# WirelessTempSensor.net
KiCad netlist of a schematic drawn in EAGLE
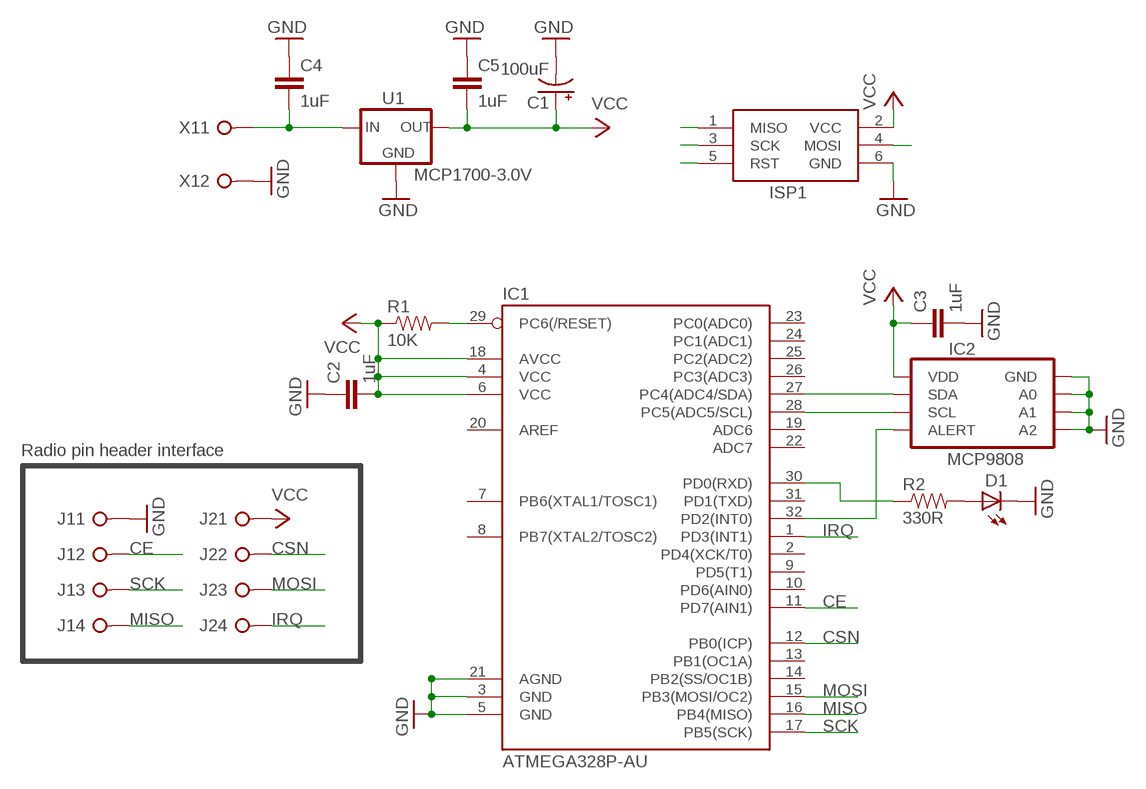
[diagram p0: schematic, sheet 1]

(export (version "E")
  (design (tool "Eeschema 10.0.6"))
  (components
    (comp (ref "C1")
      (value "100uF")
      (footprint "eagle-import:CAP-POL-2.5-6")
      (libsource (lib "eagle-import") (part "CAP-POL-2.5-6"))
    )
    (comp (ref "C2")
      (value "1uF")
      (footprint "eagle-import:CAPACITOR-0805")
      (libsource (lib "eagle-import") (part "CAPACITOR-0805"))
    )
    (comp (ref "C3")
      (value "1uF")
      (footprint "eagle-import:CAPACITOR-0805")
      (libsource (lib "eagle-import") (part "CAPACITOR-0805"))
    )
    (comp (ref "C4")
      (value "1uF")
      (footprint "eagle-import:CAPACITOR-0805")
      (libsource (lib "eagle-import") (part "CAPACITOR-0805"))
    )
    (comp (ref "C5")
      (value "1uF")
      (footprint "eagle-import:CAPACITOR-0805")
      (libsource (lib "eagle-import") (part "CAPACITOR-0805"))
    )
    (comp (ref "D1")
      (value "LED-0805")
      (footprint "eagle-import:LED-0805")
      (libsource (lib "eagle-import") (part "LED-0805"))
    )
    (comp (ref "IC1")
      (value "ATMEGA328P-AU")
      (footprint "eagle-import:QFP32-08")
      (libsource (lib "eagle-import") (part "ATMEGA328P-AU"))
    )
    (comp (ref "IC2")
      (value "MCP9808")
      (footprint "eagle-import:MSOP8-0.65-3X3MM")
      (libsource (lib "eagle-import") (part "MCP9808"))
    )
    (comp (ref "ISP1")
      (value "ICSP-HEADER-6")
      (footprint "eagle-import:ICSP-HEADER")
      (libsource (lib "eagle-import") (part "ICSP-HEADER-6"))
    )
    (comp (ref "J1")
      (value "PINHD-1X4")
      (footprint "eagle-import:1X04")
      (libsource (lib "eagle-import") (part "PINHD-1X4"))
    )
    (comp (ref "J2")
      (value "PINHD-1X4")
      (footprint "eagle-import:1X04")
      (libsource (lib "eagle-import") (part "PINHD-1X4"))
    )
    (comp (ref "R1")
      (value "10K")
      (footprint "eagle-import:RESISTOR-0805")
      (libsource (lib "eagle-import") (part "RESISTOR-0805"))
    )
    (comp (ref "R2")
      (value "330R")
      (footprint "eagle-import:RESISTOR-0805")
      (libsource (lib "eagle-import") (part "RESISTOR-0805"))
    )
    (comp (ref "U1")
      (value "MCP1700-3.0V")
      (footprint "eagle-import:SOT-23-3")
      (libsource (lib "eagle-import") (part "MCP1700-SOT23"))
    )
    (comp (ref "X1")
      (value "SCREW-TERM-2")
      (footprint "eagle-import:SCREW-TERM-2")
      (libsource (lib "eagle-import") (part "SCREW-TERM-2"))
    )
  )
  (nets
    (net (code "1") (name "/CE") (class "Default")
      (node (ref "IC1") (pin "11") (pinfunction "PD7(AIN1)_11") (pintype "bidirectional"))
      (node (ref "J1") (pin "2") (pinfunction "KL_2") (pintype "passive"))
    )
    (net (code "2") (name "/CSN") (class "Default")
      (node (ref "IC1") (pin "12") (pinfunction "PB0(ICP)_12") (pintype "bidirectional"))
      (node (ref "J2") (pin "2") (pinfunction "KL_2") (pintype "passive"))
    )
    (net (code "3") (name "/IRQ") (class "Default")
      (node (ref "IC1") (pin "1") (pinfunction "PD3(INT1)_1") (pintype "bidirectional"))
      (node (ref "J2") (pin "4") (pinfunction "KL_4") (pintype "passive"))
    )
    (net (code "4") (name "/MISO") (class "Default")
      (node (ref "IC1") (pin "16") (pinfunction "PB4(MISO)_16") (pintype "bidirectional"))
      (node (ref "ISP1") (pin "1") (pinfunction "MISO_1") (pintype "input"))
      (node (ref "J1") (pin "4") (pinfunction "KL_4") (pintype "passive"))
    )
    (net (code "5") (name "/MOSI") (class "Default")
      (node (ref "IC1") (pin "15") (pinfunction "PB3(MOSI/OC2)_15") (pintype "bidirectional"))
      (node (ref "ISP1") (pin "4") (pinfunction "MOSI_4") (pintype "output"))
      (node (ref "J2") (pin "3") (pinfunction "KL_3") (pintype "passive"))
    )
    (net (code "6") (name "/RST") (class "Default")
      (node (ref "IC1") (pin "29") (pinfunction "PC6(/RESET)_29") (pintype "bidirectional"))
      (node (ref "ISP1") (pin "5") (pinfunction "RST_5") (pintype "output"))
      (node (ref "R1") (pin "2") (pinfunction "2_2") (pintype "passive"))
    )
    (net (code "7") (name "/SCK") (class "Default")
      (node (ref "IC1") (pin "17") (pinfunction "PB5(SCK)_17") (pintype "bidirectional"))
      (node (ref "ISP1") (pin "3") (pinfunction "SCK_3") (pintype "output"))
      (node (ref "J1") (pin "3") (pinfunction "KL_3") (pintype "passive"))
    )
    (net (code "8") (name "GND") (class "Default")
      (node (ref "C1") (pin "-") (pinfunction "-_-") (pintype "passive"))
      (node (ref "C2") (pin "1") (pinfunction "1_1") (pintype "passive"))
      (node (ref "C3") (pin "2") (pinfunction "2_2") (pintype "passive"))
      (node (ref "C4") (pin "1") (pinfunction "1_1") (pintype "passive"))
      (node (ref "C5") (pin "1") (pinfunction "1_1") (pintype "passive"))
      (node (ref "D1") (pin "2") (pinfunction "C_2") (pintype "passive"))
      (node (ref "IC1") (pin "21") (pinfunction "AGND_21") (pintype "bidirectional"))
      (node (ref "IC1") (pin "3") (pinfunction "GND_3") (pintype "bidirectional"))
      (node (ref "IC1") (pin "5") (pinfunction "GND_5") (pintype "bidirectional"))
      (node (ref "IC2") (pin "4") (pinfunction "GND_4") (pintype "power_in"))
      (node (ref "IC2") (pin "5") (pinfunction "A2_5") (pintype "input"))
      (node (ref "IC2") (pin "6") (pinfunction "A1_6") (pintype "input"))
      (node (ref "IC2") (pin "7") (pinfunction "A0_7") (pintype "input"))
      (node (ref "ISP1") (pin "6") (pinfunction "GND_6") (pintype "power_in"))
      (node (ref "J1") (pin "1") (pinfunction "KL_1") (pintype "passive"))
      (node (ref "U1") (pin "1") (pinfunction "GND_1") (pintype "input"))
      (node (ref "X1") (pin "2") (pinfunction "KL_2") (pintype "passive"))
    )
    (net (code "9") (name "Net-(D1-A)") (class "Default")
      (node (ref "D1") (pin "1") (pinfunction "A_1") (pintype "passive"))
      (node (ref "R2") (pin "2") (pinfunction "2_2") (pintype "passive"))
    )
    (net (code "10") (name "Net-(IC1-PC4(ADC4{slash}SDA))") (class "Default")
      (node (ref "IC1") (pin "27") (pinfunction "PC4(ADC4/SDA)_27") (pintype "bidirectional"))
      (node (ref "IC2") (pin "1") (pinfunction "SDA_1") (pintype "bidirectional"))
    )
    (net (code "11") (name "Net-(IC1-PC5(ADC5{slash}SCL))") (class "Default")
      (node (ref "IC1") (pin "28") (pinfunction "PC5(ADC5/SCL)_28") (pintype "bidirectional"))
      (node (ref "IC2") (pin "2") (pinfunction "SCL_2") (pintype "bidirectional"))
    )
    (net (code "12") (name "Net-(IC1-PD0(RXD))") (class "Default")
      (node (ref "IC1") (pin "30") (pinfunction "PD0(RXD)_30") (pintype "bidirectional"))
      (node (ref "R2") (pin "1") (pinfunction "1_1") (pintype "passive"))
    )
    (net (code "13") (name "Net-(IC1-PD2(INT0))") (class "Default")
      (node (ref "IC1") (pin "32") (pinfunction "PD2(INT0)_32") (pintype "bidirectional"))
      (node (ref "IC2") (pin "3") (pinfunction "ALERT_3") (pintype "output"))
    )
    (net (code "14") (name "Net-(U1-IN)") (class "Default")
      (node (ref "C4") (pin "2") (pinfunction "2_2") (pintype "passive"))
      (node (ref "U1") (pin "3") (pinfunction "IN_3") (pintype "input"))
      (node (ref "X1") (pin "1") (pinfunction "KL_1") (pintype "passive"))
    )
    (net (code "15") (name "VCC") (class "Default")
      (node (ref "C1") (pin "+") (pinfunction "+_+") (pintype "passive"))
      (node (ref "C2") (pin "2") (pinfunction "2_2") (pintype "passive"))
      (node (ref "C3") (pin "1") (pinfunction "1_1") (pintype "passive"))
      (node (ref "C5") (pin "2") (pinfunction "2_2") (pintype "passive"))
      (node (ref "IC1") (pin "18") (pinfunction "AVCC_18") (pintype "bidirectional"))
      (node (ref "IC1") (pin "4") (pinfunction "VCC_4") (pintype "bidirectional"))
      (node (ref "IC1") (pin "6") (pinfunction "VCC_6") (pintype "bidirectional"))
      (node (ref "IC2") (pin "8") (pinfunction "VDD_8") (pintype "power_in"))
      (node (ref "ISP1") (pin "2") (pinfunction "VCC_2") (pintype "power_in"))
      (node (ref "J2") (pin "1") (pinfunction "KL_1") (pintype "passive"))
      (node (ref "R1") (pin "1") (pinfunction "1_1") (pintype "passive"))
      (node (ref "U1") (pin "2") (pinfunction "OUT_2") (pintype "passive"))
    )
    (net (code "16") (name "unconnected-(IC1-ADC6-Pad19)") (class "Default")
      (node (ref "IC1") (pin "19") (pinfunction "ADC6_19") (pintype "bidirectional"))
    )
    (net (code "17") (name "unconnected-(IC1-ADC7-Pad22)") (class "Default")
      (node (ref "IC1") (pin "22") (pinfunction "ADC7_22") (pintype "bidirectional"))
    )
    (net (code "18") (name "unconnected-(IC1-AREF-Pad20)") (class "Default")
      (node (ref "IC1") (pin "20") (pinfunction "AREF_20") (pintype "bidirectional"))
    )
    (net (code "19") (name "unconnected-(IC1-PB1(OC1A)-Pad13)") (class "Default")
      (node (ref "IC1") (pin "13") (pinfunction "PB1(OC1A)_13") (pintype "bidirectional"))
    )
    (net (code "20") (name "unconnected-(IC1-PB2(SS{slash}OC1B)-Pad14)") (class "Default")
      (node (ref "IC1") (pin "14") (pinfunction "PB2(SS/OC1B)_14") (pintype "bidirectional"))
    )
    (net (code "21") (name "unconnected-(IC1-PB6(XTAL1{slash}TOSC1)-Pad7)") (class "Default")
      (node (ref "IC1") (pin "7") (pinfunction "PB6(XTAL1/TOSC1)_7") (pintype "bidirectional"))
    )
    (net (code "22") (name "unconnected-(IC1-PB7(XTAL2{slash}TOSC2)-Pad8)") (class "Default")
      (node (ref "IC1") (pin "8") (pinfunction "PB7(XTAL2/TOSC2)_8") (pintype "bidirectional"))
    )
    (net (code "23") (name "unconnected-(IC1-PC0(ADC0)-Pad23)") (class "Default")
      (node (ref "IC1") (pin "23") (pinfunction "PC0(ADC0)_23") (pintype "bidirectional"))
    )
    (net (code "24") (name "unconnected-(IC1-PC1(ADC1)-Pad24)") (class "Default")
      (node (ref "IC1") (pin "24") (pinfunction "PC1(ADC1)_24") (pintype "bidirectional"))
    )
    (net (code "25") (name "unconnected-(IC1-PC2(ADC2)-Pad25)") (class "Default")
      (node (ref "IC1") (pin "25") (pinfunction "PC2(ADC2)_25") (pintype "bidirectional"))
    )
    (net (code "26") (name "unconnected-(IC1-PC3(ADC3)-Pad26)") (class "Default")
      (node (ref "IC1") (pin "26") (pinfunction "PC3(ADC3)_26") (pintype "bidirectional"))
    )
    (net (code "27") (name "unconnected-(IC1-PD1(TXD)-Pad31)") (class "Default")
      (node (ref "IC1") (pin "31") (pinfunction "PD1(TXD)_31") (pintype "bidirectional"))
    )
    (net (code "28") (name "unconnected-(IC1-PD4(XCK{slash}T0)-Pad2)") (class "Default")
      (node (ref "IC1") (pin "2") (pinfunction "PD4(XCK/T0)_2") (pintype "bidirectional"))
    )
    (net (code "29") (name "unconnected-(IC1-PD5(T1)-Pad9)") (class "Default")
      (node (ref "IC1") (pin "9") (pinfunction "PD5(T1)_9") (pintype "bidirectional"))
    )
    (net (code "30") (name "unconnected-(IC1-PD6(AIN0)-Pad10)") (class "Default")
      (node (ref "IC1") (pin "10") (pinfunction "PD6(AIN0)_10") (pintype "bidirectional"))
    )
  )
)
